# MCU.net
KiCad netlist of a schematic drawn in Altium Designer
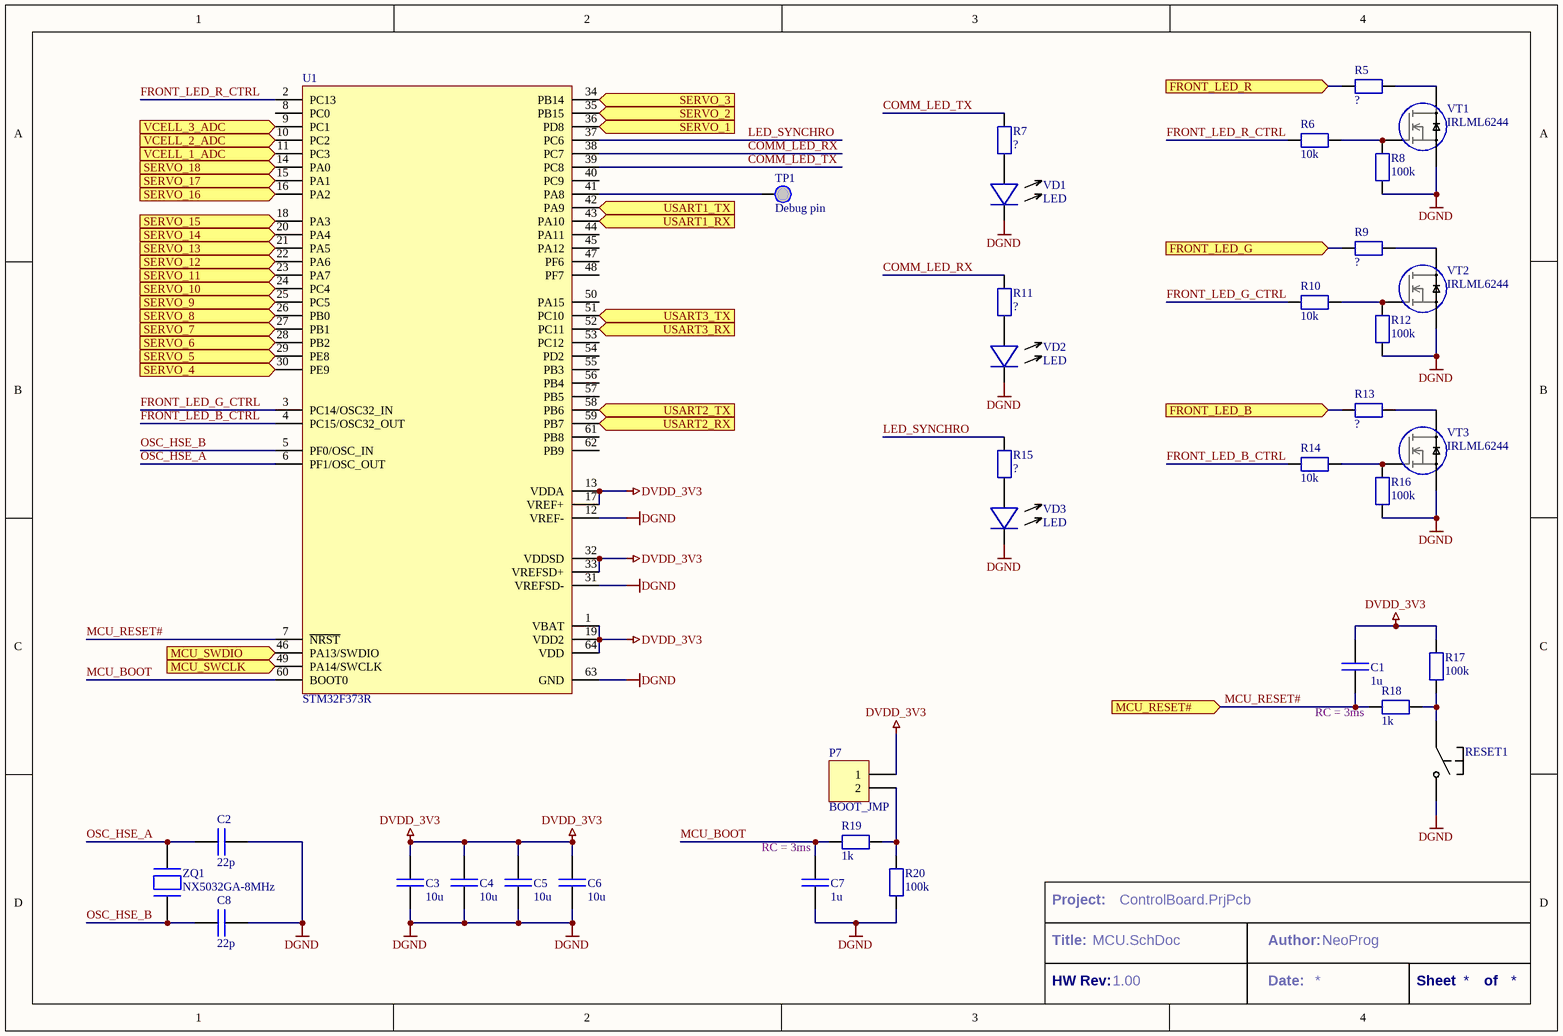
[diagram p0: MCU.SchDoc]

(export (version "E")
  (design (tool "Eeschema 10.0.6"))
  (components
    (comp (ref "C1")
      (value "1u")
      (footprint "C_0603/1608")
      (description "Non-polarized capacitor")
      (libsource (lib "passive") (part "Capacitor"))
    )
    (comp (ref "C2")
      (value "22p")
      (footprint "C_0603/1608")
      (description "Non-polarized capacitor")
      (libsource (lib "passive") (part "Capacitor"))
    )
    (comp (ref "C3")
      (value "10u")
      (footprint "C_0603/1608")
      (description "Non-polarized capacitor")
      (libsource (lib "passive") (part "Capacitor"))
    )
    (comp (ref "C4")
      (value "10u")
      (footprint "C_0603/1608")
      (description "Non-polarized capacitor")
      (libsource (lib "passive") (part "Capacitor"))
    )
    (comp (ref "C5")
      (value "10u")
      (footprint "C_0603/1608")
      (description "Non-polarized capacitor")
      (libsource (lib "passive") (part "Capacitor"))
    )
    (comp (ref "C6")
      (value "10u")
      (footprint "C_0603/1608")
      (description "Non-polarized capacitor")
      (libsource (lib "passive") (part "Capacitor"))
    )
    (comp (ref "C7")
      (value "1u")
      (footprint "C_0603/1608")
      (description "Non-polarized capacitor")
      (libsource (lib "passive") (part "Capacitor"))
    )
    (comp (ref "C8")
      (value "22p")
      (footprint "C_0603/1608")
      (description "Non-polarized capacitor")
      (libsource (lib "passive") (part "Capacitor"))
    )
    (comp (ref "P7")
      (value "BOOT_JMP")
      (footprint "HDR_SMD_1X2_1.50")
      (description "Header, 2-Pin")
      (fields (field (name "PUBLISHER") "Altium Limited"))
      (libsource (lib "connectors") (part "Header 2"))
    )
    (comp (ref "R5")
      (value "?")
      (footprint "R_0603/1608")
      (description "Resistor")
      (libsource (lib "passive") (part "Resistor"))
    )
    (comp (ref "R6")
      (value "10k")
      (footprint "R_0603/1608")
      (description "Resistor")
      (libsource (lib "passive") (part "Resistor"))
    )
    (comp (ref "R7")
      (value "?")
      (footprint "R_0603/1608")
      (description "Resistor")
      (libsource (lib "passive") (part "Resistor"))
    )
    (comp (ref "R8")
      (value "100k")
      (footprint "R_0603/1608")
      (description "Resistor")
      (libsource (lib "passive") (part "Resistor"))
    )
    (comp (ref "R9")
      (value "?")
      (footprint "R_0603/1608")
      (description "Resistor")
      (libsource (lib "passive") (part "Resistor"))
    )
    (comp (ref "R10")
      (value "10k")
      (footprint "R_0603/1608")
      (description "Resistor")
      (libsource (lib "passive") (part "Resistor"))
    )
    (comp (ref "R11")
      (value "?")
      (footprint "R_0603/1608")
      (description "Resistor")
      (libsource (lib "passive") (part "Resistor"))
    )
    (comp (ref "R12")
      (value "100k")
      (footprint "R_0603/1608")
      (description "Resistor")
      (libsource (lib "passive") (part "Resistor"))
    )
    (comp (ref "R13")
      (value "?")
      (footprint "R_0603/1608")
      (description "Resistor")
      (libsource (lib "passive") (part "Resistor"))
    )
    (comp (ref "R14")
      (value "10k")
      (footprint "R_0603/1608")
      (description "Resistor")
      (libsource (lib "passive") (part "Resistor"))
    )
    (comp (ref "R15")
      (value "?")
      (footprint "R_0603/1608")
      (description "Resistor")
      (libsource (lib "passive") (part "Resistor"))
    )
    (comp (ref "R16")
      (value "100k")
      (footprint "R_0603/1608")
      (description "Resistor")
      (libsource (lib "passive") (part "Resistor"))
    )
    (comp (ref "R17")
      (value "100k")
      (footprint "R_0603/1608")
      (description "Resistor")
      (libsource (lib "passive") (part "Resistor"))
    )
    (comp (ref "R18")
      (value "1k")
      (footprint "R_0603/1608")
      (description "Resistor")
      (libsource (lib "passive") (part "Resistor"))
    )
    (comp (ref "R19")
      (value "1k")
      (footprint "R_0603/1608")
      (description "Resistor")
      (libsource (lib "passive") (part "Resistor"))
    )
    (comp (ref "R20")
      (value "100k")
      (footprint "R_0603/1608")
      (description "Resistor")
      (libsource (lib "passive") (part "Resistor"))
    )
    (comp (ref "RESET1")
      (value "Button SPST")
      (footprint "BUTTON_SMD_6x6")
      (description "Button SPST, without fixation")
      (libsource (lib "switches") (part "Button SPST"))
    )
    (comp (ref "TP1")
      (value "Debug pin")
      (footprint "TP_SMD_D1.00")
      (description "Test point")
      (libsource (lib "connectors") (part "Test point"))
    )
    (comp (ref "U1")
      (value "STM32F373R")
      (footprint "LQFP64")
      (description "32-bit Cortex-M3")
      (libsource (lib "microcontrollers") (part "STM32F373R"))
    )
    (comp (ref "VD1") (value "LED") (footprint "LED_0603/1608") (libsource (lib "light") (part "LED")))
    (comp (ref "VD2") (value "LED") (footprint "LED_0603/1608") (libsource (lib "light") (part "LED")))
    (comp (ref "VD3") (value "LED") (footprint "LED_0603/1608") (libsource (lib "light") (part "LED")))
    (comp (ref "VT1")
      (value "IRLML6244")
      (footprint "SOT23-3")
      (description "MOSFET N")
      (libsource (lib "active") (part "MOSFET N"))
    )
    (comp (ref "VT2")
      (value "IRLML6244")
      (footprint "SOT23-3")
      (description "MOSFET N")
      (libsource (lib "active") (part "MOSFET N"))
    )
    (comp (ref "VT3")
      (value "IRLML6244")
      (footprint "SOT23-3")
      (description "MOSFET N")
      (libsource (lib "active") (part "MOSFET N"))
    )
    (comp (ref "ZQ1")
      (value "NX5032GA-8MHz")
      (footprint "OSC_2PINS SMD")
      (description "Crystal oscillator")
      (libsource (lib "passive") (part "Crystal oscillator"))
    )
  )
  (nets
    (net (code "1") (name "/COMM_LED_RX") (class "Default")
      (node (ref "R11") (pin "1") (pintype "passive"))
      (node (ref "U1") (pin "38") (pinfunction "PC7_38") (pintype "passive"))
    )
    (net (code "2") (name "/COMM_LED_TX") (class "Default")
      (node (ref "R7") (pin "1") (pintype "passive"))
      (node (ref "U1") (pin "39") (pinfunction "PC8_39") (pintype "passive"))
    )
    (net (code "3") (name "/FRONT_LED_B") (class "Default") (node (ref "R13") (pin "2") (pintype "passive")))
    (net (code "4") (name "/FRONT_LED_B_CTRL") (class "Default")
      (node (ref "R14") (pin "2") (pintype "passive"))
      (node (ref "U1") (pin "4") (pinfunction "PC15/OSC32_OUT_4") (pintype "passive"))
    )
    (net (code "5") (name "/FRONT_LED_G") (class "Default") (node (ref "R9") (pin "2") (pintype "passive")))
    (net (code "6") (name "/FRONT_LED_G_CTRL") (class "Default")
      (node (ref "R10") (pin "2") (pintype "passive"))
      (node (ref "U1") (pin "3") (pinfunction "PC14/OSC32_IN_3") (pintype "passive"))
    )
    (net (code "7") (name "/FRONT_LED_R") (class "Default") (node (ref "R5") (pin "2") (pintype "passive")))
    (net (code "8") (name "/FRONT_LED_R_CTRL") (class "Default")
      (node (ref "R6") (pin "2") (pintype "passive"))
      (node (ref "U1") (pin "2") (pinfunction "PC13_2") (pintype "passive"))
    )
    (net (code "9") (name "/LED_SYNCHRO") (class "Default")
      (node (ref "R15") (pin "1") (pintype "passive"))
      (node (ref "U1") (pin "37") (pinfunction "PC6_37") (pintype "passive"))
    )
    (net (code "10") (name "/MCU_BOOT") (class "Default")
      (node (ref "C7") (pin "1") (pintype "passive"))
      (node (ref "R19") (pin "2") (pintype "passive"))
      (node (ref "U1") (pin "60") (pinfunction "BOOT0_60") (pintype "passive"))
    )
    (net (code "11") (name "/MCU_RESET#") (class "Default")
      (node (ref "C1") (pin "2") (pintype "passive"))
      (node (ref "R18") (pin "2") (pintype "passive"))
      (node (ref "U1") (pin "7") (pinfunction "~{NRST}_7") (pintype "passive"))
    )
    (net (code "12") (name "/MCU_SWCLK") (class "Default")
      (node (ref "U1") (pin "49") (pinfunction "PA14/SWCLK_49") (pintype "passive"))
    )
    (net (code "13") (name "/MCU_SWDIO") (class "Default")
      (node (ref "U1") (pin "46") (pinfunction "PA13/SWDIO_46") (pintype "passive"))
    )
    (net (code "14") (name "/OSC_HSE_A") (class "Default")
      (node (ref "C2") (pin "1") (pintype "passive"))
      (node (ref "U1") (pin "6") (pinfunction "PF1/OSC_OUT_6") (pintype "passive"))
      (node (ref "ZQ1") (pin "2") (pintype "passive"))
    )
    (net (code "15") (name "/OSC_HSE_B") (class "Default")
      (node (ref "C8") (pin "1") (pintype "passive"))
      (node (ref "U1") (pin "5") (pinfunction "PF0/OSC_IN_5") (pintype "passive"))
      (node (ref "ZQ1") (pin "1") (pintype "passive"))
    )
    (net (code "16") (name "/SERVO_1") (class "Default")
      (node (ref "U1") (pin "36") (pinfunction "PD8_36") (pintype "passive"))
    )
    (net (code "17") (name "/SERVO_2") (class "Default")
      (node (ref "U1") (pin "35") (pinfunction "PB15_35") (pintype "passive"))
    )
    (net (code "18") (name "/SERVO_3") (class "Default")
      (node (ref "U1") (pin "34") (pinfunction "PB14_34") (pintype "passive"))
    )
    (net (code "19") (name "/SERVO_4") (class "Default")
      (node (ref "U1") (pin "30") (pinfunction "PE9_30") (pintype "passive"))
    )
    (net (code "20") (name "/SERVO_5") (class "Default")
      (node (ref "U1") (pin "29") (pinfunction "PE8_29") (pintype "passive"))
    )
    (net (code "21") (name "/SERVO_6") (class "Default")
      (node (ref "U1") (pin "28") (pinfunction "PB2_28") (pintype "passive"))
    )
    (net (code "22") (name "/SERVO_7") (class "Default")
      (node (ref "U1") (pin "27") (pinfunction "PB1_27") (pintype "passive"))
    )
    (net (code "23") (name "/SERVO_8") (class "Default")
      (node (ref "U1") (pin "26") (pinfunction "PB0_26") (pintype "passive"))
    )
    (net (code "24") (name "/SERVO_9") (class "Default")
      (node (ref "U1") (pin "25") (pinfunction "PC5_25") (pintype "passive"))
    )
    (net (code "25") (name "/SERVO_10") (class "Default")
      (node (ref "U1") (pin "24") (pinfunction "PC4_24") (pintype "passive"))
    )
    (net (code "26") (name "/SERVO_11") (class "Default")
      (node (ref "U1") (pin "23") (pinfunction "PA7_23") (pintype "passive"))
    )
    (net (code "27") (name "/SERVO_12") (class "Default")
      (node (ref "U1") (pin "22") (pinfunction "PA6_22") (pintype "passive"))
    )
    (net (code "28") (name "/SERVO_13") (class "Default")
      (node (ref "U1") (pin "21") (pinfunction "PA5_21") (pintype "passive"))
    )
    (net (code "29") (name "/SERVO_14") (class "Default")
      (node (ref "U1") (pin "20") (pinfunction "PA4_20") (pintype "passive"))
    )
    (net (code "30") (name "/SERVO_15") (class "Default")
      (node (ref "U1") (pin "18") (pinfunction "PA3_18") (pintype "passive"))
    )
    (net (code "31") (name "/SERVO_16") (class "Default")
      (node (ref "U1") (pin "16") (pinfunction "PA2_16") (pintype "passive"))
    )
    (net (code "32") (name "/SERVO_17") (class "Default")
      (node (ref "U1") (pin "15") (pinfunction "PA1_15") (pintype "passive"))
    )
    (net (code "33") (name "/SERVO_18") (class "Default")
      (node (ref "U1") (pin "14") (pinfunction "PA0_14") (pintype "passive"))
    )
    (net (code "34") (name "/USART1_RX") (class "Default")
      (node (ref "U1") (pin "43") (pinfunction "PA10_43") (pintype "passive"))
    )
    (net (code "35") (name "/USART1_TX") (class "Default")
      (node (ref "U1") (pin "42") (pinfunction "PA9_42") (pintype "passive"))
    )
    (net (code "36") (name "/USART2_RX") (class "Default")
      (node (ref "U1") (pin "59") (pinfunction "PB7_59") (pintype "passive"))
    )
    (net (code "37") (name "/USART2_TX") (class "Default")
      (node (ref "U1") (pin "58") (pinfunction "PB6_58") (pintype "passive"))
    )
    (net (code "38") (name "/USART3_RX") (class "Default")
      (node (ref "U1") (pin "52") (pinfunction "PC11_52") (pintype "passive"))
    )
    (net (code "39") (name "/USART3_TX") (class "Default")
      (node (ref "U1") (pin "51") (pinfunction "PC10_51") (pintype "passive"))
    )
    (net (code "40") (name "/VCELL_1_ADC") (class "Default")
      (node (ref "U1") (pin "11") (pinfunction "PC3_11") (pintype "passive"))
    )
    (net (code "41") (name "/VCELL_2_ADC") (class "Default")
      (node (ref "U1") (pin "10") (pinfunction "PC2_10") (pintype "passive"))
    )
    (net (code "42") (name "/VCELL_3_ADC") (class "Default")
      (node (ref "U1") (pin "9") (pinfunction "PC1_9") (pintype "passive"))
    )
    (net (code "43") (name "DGND") (class "Default")
      (node (ref "C2") (pin "2") (pintype "passive"))
      (node (ref "C3") (pin "2") (pintype "passive"))
      (node (ref "C4") (pin "2") (pintype "passive"))
      (node (ref "C5") (pin "2") (pintype "passive"))
      (node (ref "C6") (pin "2") (pintype "passive"))
      (node (ref "C7") (pin "2") (pintype "passive"))
      (node (ref "C8") (pin "2") (pintype "passive"))
      (node (ref "R12") (pin "1") (pintype "passive"))
      (node (ref "R16") (pin "1") (pintype "passive"))
      (node (ref "R20") (pin "2") (pintype "passive"))
      (node (ref "R8") (pin "1") (pintype "passive"))
      (node (ref "RESET1") (pin "2") (pinfunction "2_2") (pintype "passive"))
      (node (ref "U1") (pin "12") (pinfunction "VREF-_12") (pintype "passive"))
      (node (ref "U1") (pin "31") (pinfunction "VREFSD-_31") (pintype "passive"))
      (node (ref "U1") (pin "63") (pinfunction "GND_63") (pintype "passive"))
      (node (ref "VD1") (pin "C") (pinfunction "Cathode_C") (pintype "passive"))
      (node (ref "VD2") (pin "C") (pinfunction "Cathode_C") (pintype "passive"))
      (node (ref "VD3") (pin "C") (pinfunction "Cathode_C") (pintype "passive"))
      (node (ref "VT1") (pin "S") (pintype "passive"))
      (node (ref "VT2") (pin "S") (pintype "passive"))
      (node (ref "VT3") (pin "S") (pintype "passive"))
    )
    (net (code "44") (name "DVDD_3V3") (class "Default")
      (node (ref "C1") (pin "1") (pintype "passive"))
      (node (ref "C3") (pin "1") (pintype "passive"))
      (node (ref "C4") (pin "1") (pintype "passive"))
      (node (ref "C5") (pin "1") (pintype "passive"))
      (node (ref "C6") (pin "1") (pintype "passive"))
      (node (ref "P7") (pin "1") (pinfunction "1_1") (pintype "passive"))
      (node (ref "R17") (pin "1") (pintype "passive"))
      (node (ref "U1") (pin "1") (pinfunction "VBAT_1") (pintype "passive"))
      (node (ref "U1") (pin "13") (pinfunction "VDDA_13") (pintype "passive"))
      (node (ref "U1") (pin "17") (pinfunction "VREF+_17") (pintype "passive"))
      (node (ref "U1") (pin "19") (pinfunction "VDD2_19") (pintype "passive"))
      (node (ref "U1") (pin "32") (pinfunction "VDDSD_32") (pintype "passive"))
      (node (ref "U1") (pin "33") (pinfunction "VREFSD+_33") (pintype "passive"))
      (node (ref "U1") (pin "64") (pinfunction "VDD_64") (pintype "passive"))
    )
    (net (code "45") (name "Net-(P7-Pad2)") (class "Default")
      (node (ref "P7") (pin "2") (pinfunction "2_2") (pintype "passive"))
      (node (ref "R19") (pin "1") (pintype "passive"))
      (node (ref "R20") (pin "1") (pintype "passive"))
    )
    (net (code "46") (name "Net-(R5-Pad1)") (class "Default")
      (node (ref "R5") (pin "1") (pintype "passive"))
      (node (ref "VT1") (pin "D") (pintype "passive"))
    )
    (net (code "47") (name "Net-(R6-Pad1)") (class "Default")
      (node (ref "R6") (pin "1") (pintype "passive"))
      (node (ref "R8") (pin "2") (pintype "passive"))
      (node (ref "VT1") (pin "G") (pintype "passive"))
    )
    (net (code "48") (name "Net-(R9-Pad1)") (class "Default")
      (node (ref "R9") (pin "1") (pintype "passive"))
      (node (ref "VT2") (pin "D") (pintype "passive"))
    )
    (net (code "49") (name "Net-(R10-Pad1)") (class "Default")
      (node (ref "R10") (pin "1") (pintype "passive"))
      (node (ref "R12") (pin "2") (pintype "passive"))
      (node (ref "VT2") (pin "G") (pintype "passive"))
    )
    (net (code "50") (name "Net-(R13-Pad1)") (class "Default")
      (node (ref "R13") (pin "1") (pintype "passive"))
      (node (ref "VT3") (pin "D") (pintype "passive"))
    )
    (net (code "51") (name "Net-(R14-Pad1)") (class "Default")
      (node (ref "R14") (pin "1") (pintype "passive"))
      (node (ref "R16") (pin "2") (pintype "passive"))
      (node (ref "VT3") (pin "G") (pintype "passive"))
    )
    (net (code "52") (name "Net-(R17-Pad2)") (class "Default")
      (node (ref "R17") (pin "2") (pintype "passive"))
      (node (ref "R18") (pin "1") (pintype "passive"))
      (node (ref "RESET1") (pin "1") (pinfunction "1_1") (pintype "passive"))
    )
    (net (code "53") (name "Net-(U1-PA8)") (class "Default")
      (node (ref "TP1") (pin "1") (pintype "passive"))
      (node (ref "U1") (pin "41") (pinfunction "PA8_41") (pintype "passive"))
    )
    (net (code "54") (name "Net-(VD1-Anode)") (class "Default")
      (node (ref "R7") (pin "2") (pintype "passive"))
      (node (ref "VD1") (pin "A") (pinfunction "Anode_A") (pintype "passive"))
    )
    (net (code "55") (name "Net-(VD2-Anode)") (class "Default")
      (node (ref "R11") (pin "2") (pintype "passive"))
      (node (ref "VD2") (pin "A") (pinfunction "Anode_A") (pintype "passive"))
    )
    (net (code "56") (name "Net-(VD3-Anode)") (class "Default")
      (node (ref "R15") (pin "2") (pintype "passive"))
      (node (ref "VD3") (pin "A") (pinfunction "Anode_A") (pintype "passive"))
    )
    (net (code "57") (name "unconnected-(U1-EP-Pad0)") (class "Default")
      (node (ref "U1") (pin "0") (pinfunction "EP_0") (pintype "passive"))
    )
    (net (code "58") (name "unconnected-(U1-PA11-Pad44)") (class "Default")
      (node (ref "U1") (pin "44") (pinfunction "PA11_44") (pintype "passive"))
    )
    (net (code "59") (name "unconnected-(U1-PA12-Pad45)") (class "Default")
      (node (ref "U1") (pin "45") (pinfunction "PA12_45") (pintype "passive"))
    )
    (net (code "60") (name "unconnected-(U1-PA15-Pad50)") (class "Default")
      (node (ref "U1") (pin "50") (pinfunction "PA15_50") (pintype "passive"))
    )
    (net (code "61") (name "unconnected-(U1-PB3-Pad55)") (class "Default")
      (node (ref "U1") (pin "55") (pinfunction "PB3_55") (pintype "passive"))
    )
    (net (code "62") (name "unconnected-(U1-PB4-Pad56)") (class "Default")
      (node (ref "U1") (pin "56") (pinfunction "PB4_56") (pintype "passive"))
    )
    (net (code "63") (name "unconnected-(U1-PB5-Pad57)") (class "Default")
      (node (ref "U1") (pin "57") (pinfunction "PB5_57") (pintype "passive"))
    )
    (net (code "64") (name "unconnected-(U1-PB8-Pad61)") (class "Default")
      (node (ref "U1") (pin "61") (pinfunction "PB8_61") (pintype "passive"))
    )
    (net (code "65") (name "unconnected-(U1-PB9-Pad62)") (class "Default")
      (node (ref "U1") (pin "62") (pinfunction "PB9_62") (pintype "passive"))
    )
    (net (code "66") (name "unconnected-(U1-PC0-Pad8)") (class "Default")
      (node (ref "U1") (pin "8") (pinfunction "PC0_8") (pintype "passive"))
    )
    (net (code "67") (name "unconnected-(U1-PC9-Pad40)") (class "Default")
      (node (ref "U1") (pin "40") (pinfunction "PC9_40") (pintype "passive"))
    )
    (net (code "68") (name "unconnected-(U1-PC12-Pad53)") (class "Default")
      (node (ref "U1") (pin "53") (pinfunction "PC12_53") (pintype "passive"))
    )
    (net (code "69") (name "unconnected-(U1-PD2-Pad54)") (class "Default")
      (node (ref "U1") (pin "54") (pinfunction "PD2_54") (pintype "passive"))
    )
    (net (code "70") (name "unconnected-(U1-PF6-Pad47)") (class "Default")
      (node (ref "U1") (pin "47") (pinfunction "PF6_47") (pintype "passive"))
    )
    (net (code "71") (name "unconnected-(U1-PF7-Pad48)") (class "Default")
      (node (ref "U1") (pin "48") (pinfunction "PF7_48") (pintype "passive"))
    )
  )
)
